# stm32_bord.net
KiCad netlist of a schematic drawn in EAGLE
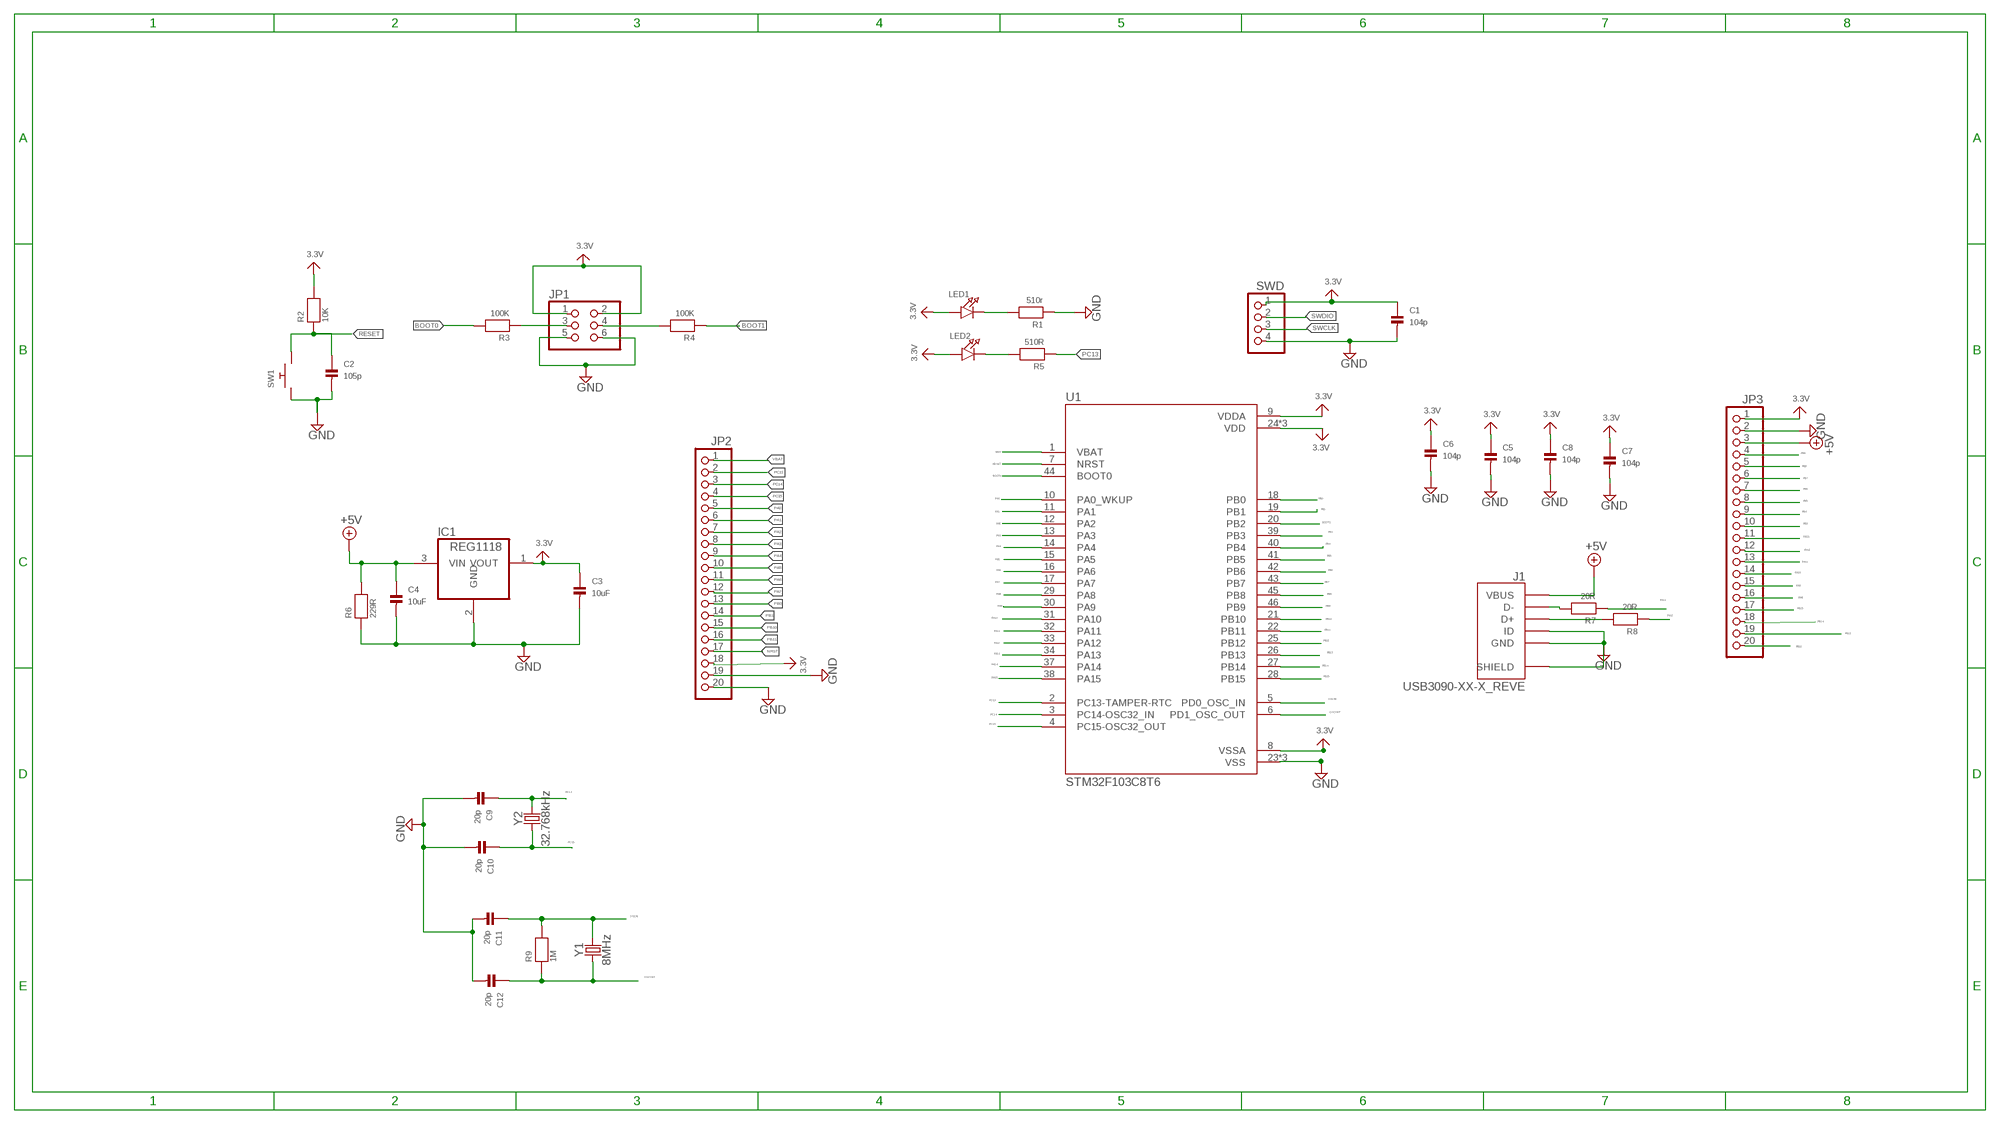
[diagram p0: schematic, sheet 1]

(export (version "E")
  (design (tool "Eeschema 10.0.6"))
  (components
    (comp (ref "C1")
      (value "104p")
      (footprint "eagle-import:_0603")
      (libsource (lib "eagle-import") (part "CAP_CERAMIC_0603"))
    )
    (comp (ref "C2")
      (value "105p")
      (footprint "eagle-import:_0603")
      (libsource (lib "eagle-import") (part "CAP_CERAMIC_0603"))
    )
    (comp (ref "C3")
      (value "10uF")
      (footprint "eagle-import:_0603")
      (libsource (lib "eagle-import") (part "CAP_CERAMIC_0603"))
    )
    (comp (ref "C4")
      (value "10uF")
      (footprint "eagle-import:_0603")
      (libsource (lib "eagle-import") (part "CAP_CERAMIC_0603"))
    )
    (comp (ref "C5")
      (value "104p")
      (footprint "eagle-import:_0603")
      (libsource (lib "eagle-import") (part "CAP_CERAMIC_0603"))
    )
    (comp (ref "C6")
      (value "104p")
      (footprint "eagle-import:_0603")
      (libsource (lib "eagle-import") (part "CAP_CERAMIC_0603"))
    )
    (comp (ref "C7")
      (value "104p")
      (footprint "eagle-import:_0603")
      (libsource (lib "eagle-import") (part "CAP_CERAMIC_0603"))
    )
    (comp (ref "C8")
      (value "104p")
      (footprint "eagle-import:_0603")
      (libsource (lib "eagle-import") (part "CAP_CERAMIC_0603"))
    )
    (comp (ref "C9")
      (value "20p")
      (footprint "eagle-import:_0603")
      (libsource (lib "eagle-import") (part "CAP_CERAMIC_0603"))
    )
    (comp (ref "C10")
      (value "20p")
      (footprint "eagle-import:_0603")
      (libsource (lib "eagle-import") (part "CAP_CERAMIC_0603"))
    )
    (comp (ref "C11")
      (value "20p")
      (footprint "eagle-import:_0603")
      (libsource (lib "eagle-import") (part "CAP_CERAMIC_0603"))
    )
    (comp (ref "C12")
      (value "20p")
      (footprint "eagle-import:_0603")
      (libsource (lib "eagle-import") (part "CAP_CERAMIC_0603"))
    )
    (comp (ref "IC1")
      (value "REG1118")
      (footprint "eagle-import:SOT223")
      (fields (field (name "MPN") "REG1118-2.85/2K5G4"))
      (libsource (lib "eagle-import") (part "REG1118"))
    )
    (comp (ref "J1")
      (value "USB3090-XX-X_REVE")
      (footprint "eagle-import:GCT_USB3090-XX-X_REVE")
      (fields (field (name "MF") "Global Connector Technology") (field (name "MP") "USB3090-30-A"))
      (libsource (lib "eagle-import") (part "USB3090-XX-X_REVE"))
    )
    (comp (ref "JP1")
      (value "PINHD-2X3")
      (footprint "eagle-import:2X03")
      (libsource (lib "eagle-import") (part "PINHD-2X3"))
    )
    (comp (ref "JP2")
      (value "PINHD-1X20")
      (footprint "eagle-import:1X20")
      (libsource (lib "eagle-import") (part "PINHD-1X20"))
    )
    (comp (ref "JP3")
      (value "PINHD-1X20")
      (footprint "eagle-import:1X20")
      (libsource (lib "eagle-import") (part "PINHD-1X20"))
    )
    (comp (ref "LED1")
      (value "LED0603")
      (footprint "eagle-import:CHIPLED_0603")
      (libsource (lib "eagle-import") (part "LED0603"))
    )
    (comp (ref "LED2")
      (value "LED0603")
      (footprint "eagle-import:CHIPLED_0603")
      (libsource (lib "eagle-import") (part "LED0603"))
    )
    (comp (ref "R1")
      (value "510r")
      (footprint "eagle-import:0603")
      (libsource (lib "eagle-import") (part "RESISTOR0603"))
    )
    (comp (ref "R2")
      (value "10K")
      (footprint "eagle-import:0603")
      (libsource (lib "eagle-import") (part "RESISTOR0603"))
    )
    (comp (ref "R3")
      (value "100K")
      (footprint "eagle-import:0603")
      (libsource (lib "eagle-import") (part "RESISTOR0603"))
    )
    (comp (ref "R4")
      (value "100K")
      (footprint "eagle-import:0603")
      (libsource (lib "eagle-import") (part "RESISTOR0603"))
    )
    (comp (ref "R5")
      (value "510R")
      (footprint "eagle-import:0603")
      (libsource (lib "eagle-import") (part "RESISTOR0603"))
    )
    (comp (ref "R6")
      (value "229R")
      (footprint "eagle-import:0603")
      (libsource (lib "eagle-import") (part "RESISTOR0603"))
    )
    (comp (ref "R7")
      (value "20R")
      (footprint "eagle-import:0603")
      (libsource (lib "eagle-import") (part "RESISTOR0603"))
    )
    (comp (ref "R8")
      (value "20R")
      (footprint "eagle-import:0603")
      (libsource (lib "eagle-import") (part "RESISTOR0603"))
    )
    (comp (ref "R9")
      (value "1M")
      (footprint "eagle-import:0603")
      (libsource (lib "eagle-import") (part "RESISTOR0603"))
    )
    (comp (ref "SW1")
      (value "SWITCH_PUSHBUTTONSOFTTOUCHSMD_SJ")
      (footprint "eagle-import:PUSHBUTTON_SMD_SJ")
      (libsource (lib "eagle-import") (part "SWITCH_PUSHBUTTONSOFTTOUCHSMD_SJ"))
    )
    (comp (ref "SWD")
      (value "PINHD-1X4")
      (footprint "eagle-import:1X04")
      (libsource (lib "eagle-import") (part "PINHD-1X4"))
    )
    (comp (ref "U1")
      (value "STM32F103C8T6")
      (footprint "eagle-import:QFP50P900X900X160-48N")
      (fields (field (name "MF") "STMicroelectronics"))
      (libsource (lib "eagle-import") (part "STM32F103C8T6"))
    )
    (comp (ref "Y1")
      (value "8MHz")
      (footprint "eagle-import:CRYSTAL-SMD-2X6-CYL")
      (libsource (lib "eagle-import") (part "CRYSTAL-32.768KHZSMD-2X6"))
    )
    (comp (ref "Y2")
      (value "32.768kHz")
      (footprint "eagle-import:CRYSTAL-SMD-2X6-CYL")
      (libsource (lib "eagle-import") (part "CRYSTAL-32.768KHZSMD-2X6"))
    )
  )
  (nets
    (net (code "1") (name "+5V") (class "Default")
      (node (ref "C4") (pin "1") (pinfunction "P$1_1") (pintype "passive"))
      (node (ref "IC1") (pin "3") (pinfunction "VIN_3") (pintype "input"))
      (node (ref "J1") (pin "1") (pinfunction "VBUS_1") (pintype "power_in"))
      (node (ref "JP3") (pin "3") (pinfunction "3_3") (pintype "passive"))
      (node (ref "R6") (pin "2") (pinfunction "2_2") (pintype "passive"))
    )
    (net (code "2") (name "/OSCIN") (class "Default")
      (node (ref "C11") (pin "1") (pinfunction "P$1_1") (pintype "passive"))
      (node (ref "R9") (pin "2") (pinfunction "2_2") (pintype "passive"))
      (node (ref "U1") (pin "5") (pinfunction "PD0_OSC_IN_5") (pintype "bidirectional"))
      (node (ref "Y1") (pin "X2") (pinfunction "2_X2") (pintype "passive"))
    )
    (net (code "3") (name "/OSCOUT") (class "Default")
      (node (ref "C12") (pin "1") (pinfunction "P$1_1") (pintype "passive"))
      (node (ref "R9") (pin "1") (pinfunction "1_1") (pintype "passive"))
      (node (ref "U1") (pin "6") (pinfunction "PD1_OSC_OUT_6") (pintype "bidirectional"))
      (node (ref "Y1") (pin "X1") (pinfunction "1_X1") (pintype "passive"))
    )
    (net (code "4") (name "/PA8") (class "Default")
      (node (ref "JP3") (pin "16") (pinfunction "16_16") (pintype "passive"))
      (node (ref "U1") (pin "29") (pinfunction "PA8_29") (pintype "bidirectional"))
    )
    (net (code "5") (name "/PA9") (class "Default")
      (node (ref "JP3") (pin "15") (pinfunction "15_15") (pintype "passive"))
      (node (ref "U1") (pin "30") (pinfunction "PA9_30") (pintype "bidirectional"))
    )
    (net (code "6") (name "/PA10") (class "Default")
      (node (ref "JP3") (pin "14") (pinfunction "14_14") (pintype "passive"))
      (node (ref "U1") (pin "31") (pinfunction "PA10_31") (pintype "bidirectional"))
    )
    (net (code "7") (name "/PA11") (class "Default")
      (node (ref "JP3") (pin "13") (pinfunction "13_13") (pintype "passive"))
      (node (ref "R7") (pin "1") (pinfunction "1_1") (pintype "passive"))
      (node (ref "U1") (pin "32") (pinfunction "PA11_32") (pintype "bidirectional"))
    )
    (net (code "8") (name "/PA12") (class "Default")
      (node (ref "JP3") (pin "12") (pinfunction "12_12") (pintype "passive"))
      (node (ref "R8") (pin "1") (pinfunction "1_1") (pintype "passive"))
      (node (ref "U1") (pin "33") (pinfunction "PA12_33") (pintype "bidirectional"))
    )
    (net (code "9") (name "/PA13") (class "Default")
      (node (ref "U1") (pin "34") (pinfunction "PA13_34") (pintype "bidirectional"))
    )
    (net (code "10") (name "/PA14") (class "Default")
      (node (ref "U1") (pin "37") (pinfunction "PA14_37") (pintype "bidirectional"))
    )
    (net (code "11") (name "/PA15") (class "Default")
      (node (ref "JP3") (pin "11") (pinfunction "11_11") (pintype "passive"))
      (node (ref "U1") (pin "38") (pinfunction "PA15_38") (pintype "bidirectional"))
    )
    (net (code "12") (name "/PB3") (class "Default")
      (node (ref "JP3") (pin "10") (pinfunction "10_10") (pintype "passive"))
      (node (ref "U1") (pin "39") (pinfunction "PB3_39") (pintype "bidirectional"))
    )
    (net (code "13") (name "/PB4") (class "Default")
      (node (ref "JP3") (pin "9") (pinfunction "9_9") (pintype "passive"))
      (node (ref "U1") (pin "40") (pinfunction "PB4_40") (pintype "bidirectional"))
    )
    (net (code "14") (name "/PB5") (class "Default")
      (node (ref "JP3") (pin "8") (pinfunction "8_8") (pintype "passive"))
      (node (ref "U1") (pin "41") (pinfunction "PB5_41") (pintype "bidirectional"))
    )
    (net (code "15") (name "/PB6") (class "Default")
      (node (ref "JP3") (pin "7") (pinfunction "7_7") (pintype "passive"))
      (node (ref "U1") (pin "42") (pinfunction "PB6_42") (pintype "bidirectional"))
    )
    (net (code "16") (name "/PB7") (class "Default")
      (node (ref "JP3") (pin "6") (pinfunction "6_6") (pintype "passive"))
      (node (ref "U1") (pin "43") (pinfunction "PB7_43") (pintype "bidirectional"))
    )
    (net (code "17") (name "/PB8") (class "Default")
      (node (ref "JP3") (pin "5") (pinfunction "5_5") (pintype "passive"))
      (node (ref "U1") (pin "45") (pinfunction "PB8_45") (pintype "bidirectional"))
    )
    (net (code "18") (name "/PB9") (class "Default")
      (node (ref "JP3") (pin "4") (pinfunction "4_4") (pintype "passive"))
      (node (ref "U1") (pin "46") (pinfunction "PB9_46") (pintype "bidirectional"))
    )
    (net (code "19") (name "/PB12") (class "Default")
      (node (ref "JP3") (pin "20") (pinfunction "20_20") (pintype "passive"))
      (node (ref "U1") (pin "25") (pinfunction "PB12_25") (pintype "bidirectional"))
    )
    (net (code "20") (name "/PB13") (class "Default")
      (node (ref "JP3") (pin "19") (pinfunction "19_19") (pintype "passive"))
      (node (ref "U1") (pin "26") (pinfunction "PB13_26") (pintype "bidirectional"))
    )
    (net (code "21") (name "/PB14") (class "Default")
      (node (ref "JP3") (pin "18") (pinfunction "18_18") (pintype "passive"))
      (node (ref "U1") (pin "27") (pinfunction "PB14_27") (pintype "bidirectional"))
    )
    (net (code "22") (name "/PB15") (class "Default")
      (node (ref "JP3") (pin "17") (pinfunction "17_17") (pintype "passive"))
      (node (ref "U1") (pin "28") (pinfunction "PB15_28") (pintype "bidirectional"))
    )
    (net (code "23") (name "3.3V") (class "Default")
      (node (ref "C1") (pin "1") (pinfunction "P$1_1") (pintype "passive"))
      (node (ref "C3") (pin "1") (pinfunction "P$1_1") (pintype "passive"))
      (node (ref "C5") (pin "1") (pinfunction "P$1_1") (pintype "passive"))
      (node (ref "C6") (pin "1") (pinfunction "P$1_1") (pintype "passive"))
      (node (ref "C7") (pin "1") (pinfunction "P$1_1") (pintype "passive"))
      (node (ref "C8") (pin "1") (pinfunction "P$1_1") (pintype "passive"))
      (node (ref "IC1") (pin "1") (pinfunction "VOUT_1") (pintype "output"))
      (node (ref "JP1") (pin "1") (pinfunction "1_1") (pintype "passive"))
      (node (ref "JP1") (pin "2") (pinfunction "2_2") (pintype "passive"))
      (node (ref "JP2") (pin "18") (pinfunction "18_18") (pintype "passive"))
      (node (ref "JP3") (pin "1") (pinfunction "1_1") (pintype "passive"))
      (node (ref "LED1") (pin "A") (pinfunction "A_A") (pintype "passive"))
      (node (ref "LED2") (pin "A") (pinfunction "A_A") (pintype "passive"))
      (node (ref "R2") (pin "2") (pinfunction "2_2") (pintype "passive"))
      (node (ref "SWD") (pin "1") (pinfunction "1_1") (pintype "passive"))
      (node (ref "U1") (pin "24") (pinfunction "VDD_24") (pintype "power_in"))
      (node (ref "U1") (pin "36") (pinfunction "VDD_36") (pintype "power_in"))
      (node (ref "U1") (pin "48") (pinfunction "VDD_48") (pintype "power_in"))
      (node (ref "U1") (pin "8") (pinfunction "VSSA_8") (pintype "power_in"))
      (node (ref "U1") (pin "9") (pinfunction "VDDA_9") (pintype "power_in"))
    )
    (net (code "24") (name "BOOT0") (class "Default")
      (node (ref "R3") (pin "2") (pinfunction "2_2") (pintype "passive"))
      (node (ref "U1") (pin "44") (pinfunction "BOOT0_44") (pintype "input"))
    )
    (net (code "25") (name "BOOT1") (class "Default")
      (node (ref "R4") (pin "1") (pinfunction "1_1") (pintype "passive"))
      (node (ref "U1") (pin "20") (pinfunction "PB2_20") (pintype "bidirectional"))
    )
    (net (code "26") (name "GND") (class "Default")
      (node (ref "C1") (pin "2") (pinfunction "P$2_2") (pintype "passive"))
      (node (ref "C10") (pin "2") (pinfunction "P$2_2") (pintype "passive"))
      (node (ref "C11") (pin "2") (pinfunction "P$2_2") (pintype "passive"))
      (node (ref "C12") (pin "2") (pinfunction "P$2_2") (pintype "passive"))
      (node (ref "C2") (pin "2") (pinfunction "P$2_2") (pintype "passive"))
      (node (ref "C3") (pin "2") (pinfunction "P$2_2") (pintype "passive"))
      (node (ref "C4") (pin "2") (pinfunction "P$2_2") (pintype "passive"))
      (node (ref "C5") (pin "2") (pinfunction "P$2_2") (pintype "passive"))
      (node (ref "C6") (pin "2") (pinfunction "P$2_2") (pintype "passive"))
      (node (ref "C7") (pin "2") (pinfunction "P$2_2") (pintype "passive"))
      (node (ref "C8") (pin "2") (pinfunction "P$2_2") (pintype "passive"))
      (node (ref "C9") (pin "2") (pinfunction "P$2_2") (pintype "passive"))
      (node (ref "IC1") (pin "2") (pinfunction "GND_2") (pintype "power_in"))
      (node (ref "J1") (pin "4") (pinfunction "ID_4") (pintype "bidirectional"))
      (node (ref "J1") (pin "5") (pinfunction "GND_5") (pintype "power_in"))
      (node (ref "J1") (pin "6") (pinfunction "SHIELD_6") (pintype "power_in"))
      (node (ref "J1") (pin "7") (pinfunction "SHIELD_7") (pintype "power_in"))
      (node (ref "J1") (pin "8") (pinfunction "SHIELD_8") (pintype "power_in"))
      (node (ref "J1") (pin "9") (pinfunction "SHIELD_9") (pintype "power_in"))
      (node (ref "JP1") (pin "5") (pinfunction "5_5") (pintype "passive"))
      (node (ref "JP1") (pin "6") (pinfunction "6_6") (pintype "passive"))
      (node (ref "JP2") (pin "19") (pinfunction "19_19") (pintype "passive"))
      (node (ref "JP2") (pin "20") (pinfunction "20_20") (pintype "passive"))
      (node (ref "JP3") (pin "2") (pinfunction "2_2") (pintype "passive"))
      (node (ref "R1") (pin "1") (pinfunction "1_1") (pintype "passive"))
      (node (ref "R6") (pin "1") (pinfunction "1_1") (pintype "passive"))
      (node (ref "SW1") (pin "P$1") (pinfunction "P$1_P$1") (pintype "passive"))
      (node (ref "SWD") (pin "4") (pinfunction "4_4") (pintype "passive"))
      (node (ref "U1") (pin "23") (pinfunction "VSS_23") (pintype "power_in"))
      (node (ref "U1") (pin "35") (pinfunction "VSS_35") (pintype "power_in"))
      (node (ref "U1") (pin "47") (pinfunction "VSS_47") (pintype "power_in"))
    )
    (net (code "27") (name "NRST") (class "Default")
      (node (ref "JP2") (pin "17") (pinfunction "17_17") (pintype "passive"))
    )
    (net (code "28") (name "Net-(J1-D+)") (class "Default")
      (node (ref "J1") (pin "3") (pinfunction "D+_3") (pintype "bidirectional"))
      (node (ref "R8") (pin "2") (pinfunction "2_2") (pintype "passive"))
    )
    (net (code "29") (name "Net-(J1-D-)") (class "Default")
      (node (ref "J1") (pin "2") (pinfunction "D-_2") (pintype "bidirectional"))
      (node (ref "R7") (pin "2") (pinfunction "2_2") (pintype "passive"))
    )
    (net (code "30") (name "Net-(JP1-Pad3)") (class "Default")
      (node (ref "JP1") (pin "3") (pinfunction "3_3") (pintype "passive"))
      (node (ref "R3") (pin "1") (pinfunction "1_1") (pintype "passive"))
    )
    (net (code "31") (name "Net-(JP1-Pad4)") (class "Default")
      (node (ref "JP1") (pin "4") (pinfunction "4_4") (pintype "passive"))
      (node (ref "R4") (pin "2") (pinfunction "2_2") (pintype "passive"))
    )
    (net (code "32") (name "Net-(LED1-PadC)") (class "Default")
      (node (ref "LED1") (pin "C") (pinfunction "C_C") (pintype "passive"))
      (node (ref "R1") (pin "2") (pinfunction "2_2") (pintype "passive"))
    )
    (net (code "33") (name "Net-(LED2-PadC)") (class "Default")
      (node (ref "LED2") (pin "C") (pinfunction "C_C") (pintype "passive"))
      (node (ref "R5") (pin "2") (pinfunction "2_2") (pintype "passive"))
    )
    (net (code "34") (name "PA0") (class "Default")
      (node (ref "JP2") (pin "5") (pinfunction "5_5") (pintype "passive"))
      (node (ref "U1") (pin "10") (pinfunction "PA0_WKUP_10") (pintype "bidirectional"))
    )
    (net (code "35") (name "PA1") (class "Default")
      (node (ref "JP2") (pin "6") (pinfunction "6_6") (pintype "passive"))
      (node (ref "U1") (pin "11") (pinfunction "PA1_11") (pintype "bidirectional"))
    )
    (net (code "36") (name "PA2") (class "Default")
      (node (ref "JP2") (pin "7") (pinfunction "7_7") (pintype "passive"))
      (node (ref "U1") (pin "12") (pinfunction "PA2_12") (pintype "bidirectional"))
    )
    (net (code "37") (name "PA3") (class "Default")
      (node (ref "JP2") (pin "8") (pinfunction "8_8") (pintype "passive"))
      (node (ref "U1") (pin "13") (pinfunction "PA3_13") (pintype "bidirectional"))
    )
    (net (code "38") (name "PA4") (class "Default")
      (node (ref "JP2") (pin "9") (pinfunction "9_9") (pintype "passive"))
      (node (ref "U1") (pin "14") (pinfunction "PA4_14") (pintype "bidirectional"))
    )
    (net (code "39") (name "PA5") (class "Default")
      (node (ref "JP2") (pin "10") (pinfunction "10_10") (pintype "passive"))
      (node (ref "U1") (pin "15") (pinfunction "PA5_15") (pintype "bidirectional"))
    )
    (net (code "40") (name "PA6") (class "Default")
      (node (ref "JP2") (pin "11") (pinfunction "11_11") (pintype "passive"))
      (node (ref "U1") (pin "16") (pinfunction "PA6_16") (pintype "bidirectional"))
    )
    (net (code "41") (name "PA7") (class "Default")
      (node (ref "JP2") (pin "12") (pinfunction "12_12") (pintype "passive"))
      (node (ref "U1") (pin "17") (pinfunction "PA7_17") (pintype "bidirectional"))
    )
    (net (code "42") (name "PB0") (class "Default")
      (node (ref "JP2") (pin "13") (pinfunction "13_13") (pintype "passive"))
      (node (ref "U1") (pin "18") (pinfunction "PB0_18") (pintype "bidirectional"))
    )
    (net (code "43") (name "PB1") (class "Default")
      (node (ref "JP2") (pin "14") (pinfunction "14_14") (pintype "passive"))
      (node (ref "U1") (pin "19") (pinfunction "PB1_19") (pintype "bidirectional"))
    )
    (net (code "44") (name "PB10") (class "Default")
      (node (ref "JP2") (pin "15") (pinfunction "15_15") (pintype "passive"))
      (node (ref "U1") (pin "21") (pinfunction "PB10_21") (pintype "bidirectional"))
    )
    (net (code "45") (name "PB11") (class "Default")
      (node (ref "JP2") (pin "16") (pinfunction "16_16") (pintype "passive"))
      (node (ref "U1") (pin "22") (pinfunction "PB11_22") (pintype "bidirectional"))
    )
    (net (code "46") (name "PC13") (class "Default")
      (node (ref "JP2") (pin "2") (pinfunction "2_2") (pintype "passive"))
      (node (ref "R5") (pin "1") (pinfunction "1_1") (pintype "passive"))
      (node (ref "U1") (pin "2") (pinfunction "PC13-TAMPER-RTC_2") (pintype "bidirectional"))
    )
    (net (code "47") (name "PC14") (class "Default")
      (node (ref "C9") (pin "1") (pinfunction "P$1_1") (pintype "passive"))
      (node (ref "JP2") (pin "3") (pinfunction "3_3") (pintype "passive"))
      (node (ref "U1") (pin "3") (pinfunction "PC14-OSC32_IN_3") (pintype "bidirectional"))
      (node (ref "Y2") (pin "X2") (pinfunction "2_X2") (pintype "passive"))
    )
    (net (code "48") (name "PC15") (class "Default")
      (node (ref "C10") (pin "1") (pinfunction "P$1_1") (pintype "passive"))
      (node (ref "JP2") (pin "4") (pinfunction "4_4") (pintype "passive"))
      (node (ref "U1") (pin "4") (pinfunction "PC15-OSC32_OUT_4") (pintype "bidirectional"))
      (node (ref "Y2") (pin "X1") (pinfunction "1_X1") (pintype "passive"))
    )
    (net (code "49") (name "RESET") (class "Default")
      (node (ref "C2") (pin "1") (pinfunction "P$1_1") (pintype "passive"))
      (node (ref "R2") (pin "1") (pinfunction "1_1") (pintype "passive"))
      (node (ref "SW1") (pin "P$2") (pinfunction "P$2_P$2") (pintype "passive"))
      (node (ref "U1") (pin "7") (pinfunction "NRST_7") (pintype "input"))
    )
    (net (code "50") (name "SWCLK") (class "Default")
      (node (ref "SWD") (pin "3") (pinfunction "3_3") (pintype "passive"))
    )
    (net (code "51") (name "SWDIO") (class "Default")
      (node (ref "SWD") (pin "2") (pinfunction "2_2") (pintype "passive"))
    )
    (net (code "52") (name "VBAT") (class "Default")
      (node (ref "JP2") (pin "1") (pinfunction "1_1") (pintype "passive"))
      (node (ref "U1") (pin "1") (pinfunction "VBAT_1") (pintype "bidirectional"))
    )
  )
)
